# nRF51x22_qfaa_dcdc.net
KiCad netlist of a schematic drawn in EAGLE
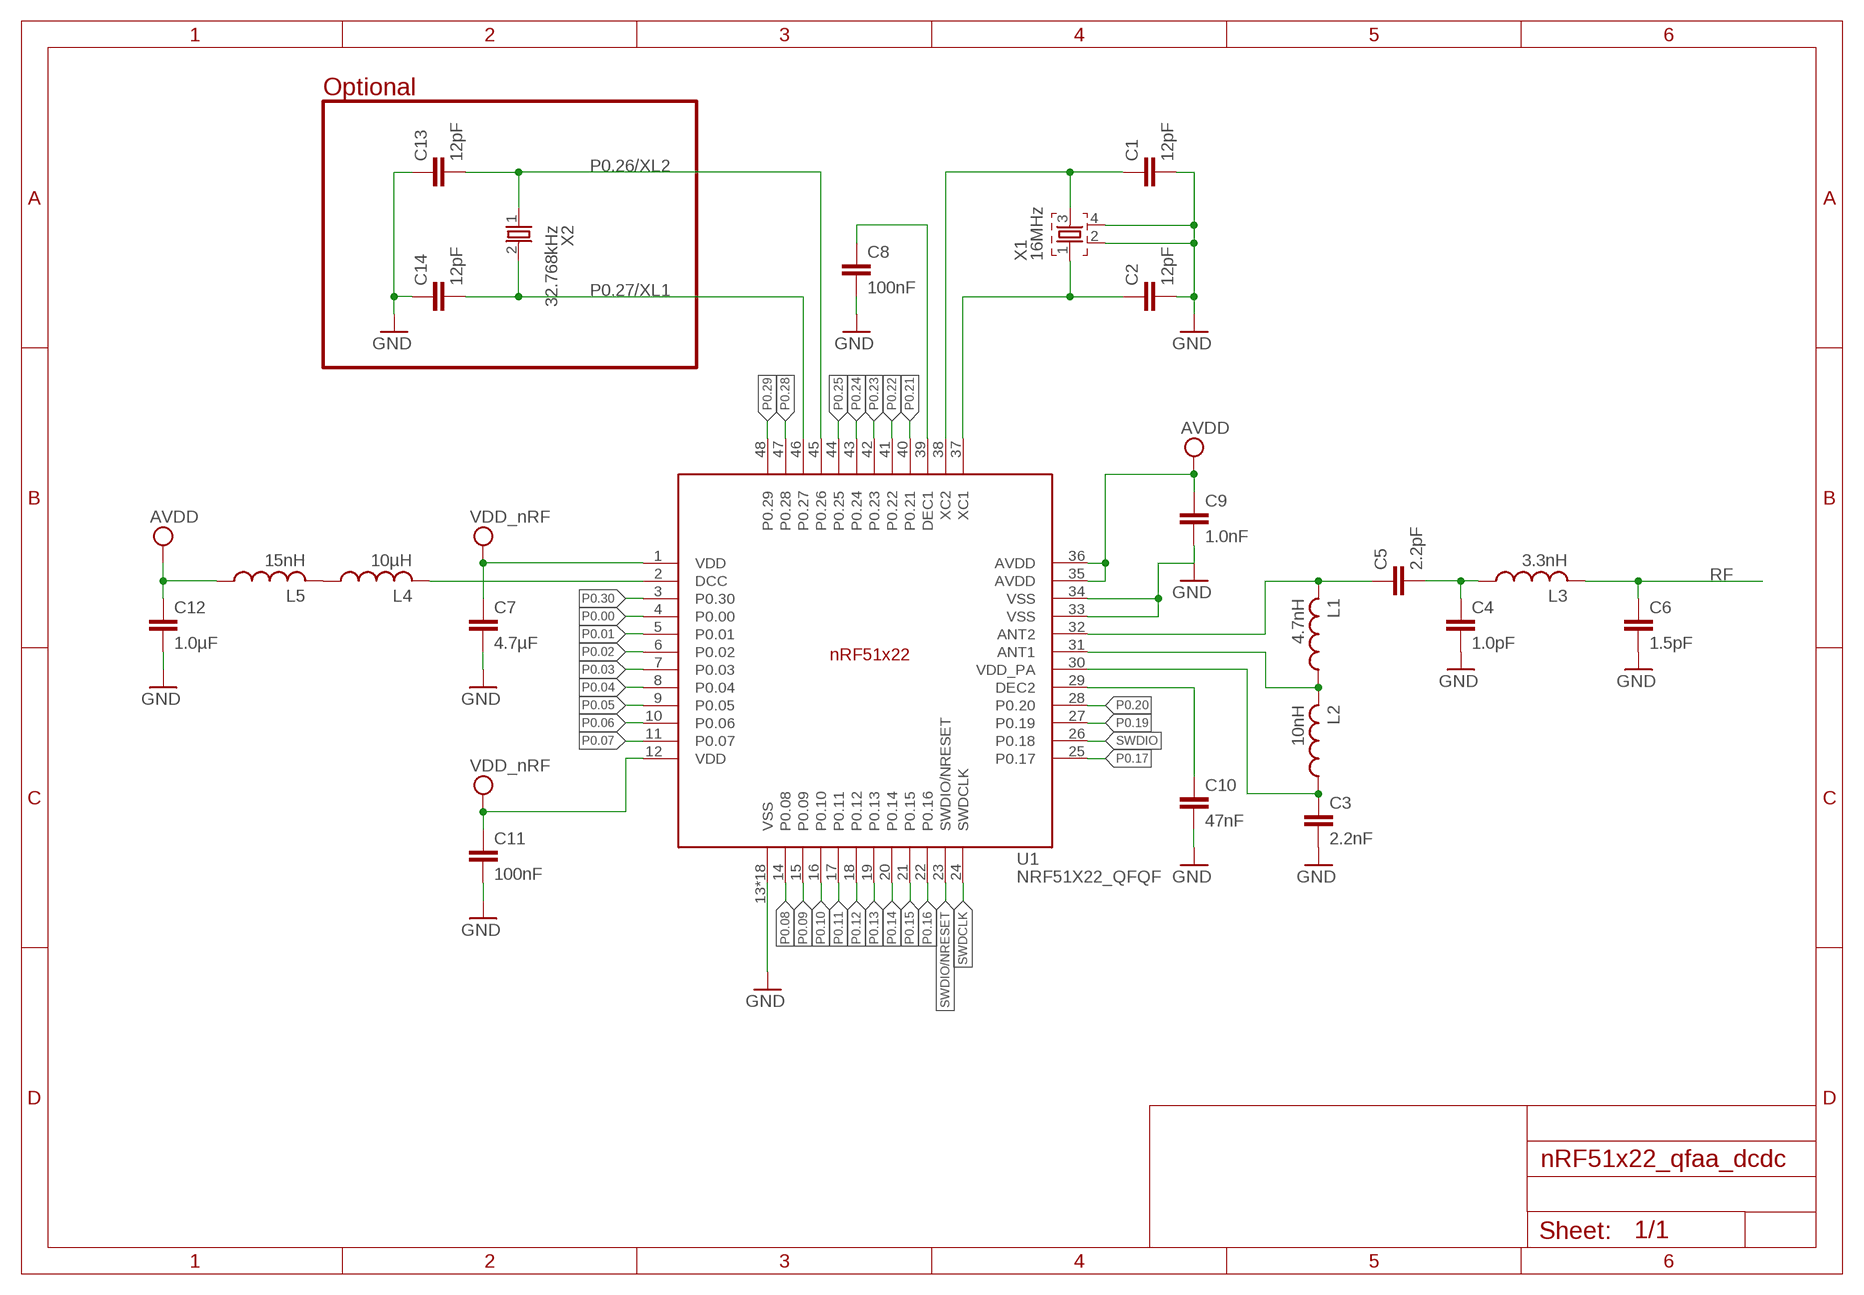
[diagram p0: schematic, sheet 1]

(export (version "E")
  (design (tool "Eeschema 10.0.6"))
  (components
    (comp (ref "C1")
      (value "12pF")
      (footprint "eagle-import:RESC0402_N")
      (libsource (lib "eagle-import") (part "CAPACITOR_0402_N"))
    )
    (comp (ref "C2")
      (value "12pF")
      (footprint "eagle-import:RESC0402_N")
      (libsource (lib "eagle-import") (part "CAPACITOR_0402_N"))
    )
    (comp (ref "C3")
      (value "2.2nF")
      (footprint "eagle-import:RESC0402_N")
      (libsource (lib "eagle-import") (part "CAPACITOR_0402_N"))
    )
    (comp (ref "C4")
      (value "1.0pF")
      (footprint "eagle-import:RESC0402_N")
      (libsource (lib "eagle-import") (part "CAPACITOR_0402_N"))
    )
    (comp (ref "C5")
      (value "2.2pF")
      (footprint "eagle-import:RESC0402_N")
      (libsource (lib "eagle-import") (part "CAPACITOR_0402_N"))
    )
    (comp (ref "C6")
      (value "1.5pF")
      (footprint "eagle-import:RESC0402_N")
      (libsource (lib "eagle-import") (part "CAPACITOR_0402_N"))
    )
    (comp (ref "C7")
      (value "4.7µF")
      (footprint "eagle-import:RESC0603_N")
      (libsource (lib "eagle-import") (part "CAPACITOR_0603_N"))
    )
    (comp (ref "C8")
      (value "100nF")
      (footprint "eagle-import:RESC0402_N")
      (libsource (lib "eagle-import") (part "CAPACITOR_0402_N"))
    )
    (comp (ref "C9")
      (value "1.0nF")
      (footprint "eagle-import:RESC0402_N")
      (libsource (lib "eagle-import") (part "CAPACITOR_0402_N"))
    )
    (comp (ref "C10")
      (value "47nF")
      (footprint "eagle-import:RESC0402_N")
      (libsource (lib "eagle-import") (part "CAPACITOR_0402_N"))
    )
    (comp (ref "C11")
      (value "100nF")
      (footprint "eagle-import:RESC0402_N")
      (libsource (lib "eagle-import") (part "CAPACITOR_0402_N"))
    )
    (comp (ref "C12")
      (value "1.0µF")
      (footprint "eagle-import:RESC0603_N")
      (libsource (lib "eagle-import") (part "CAPACITOR_0603_N"))
    )
    (comp (ref "C13")
      (value "12pF")
      (footprint "eagle-import:RESC0402_N")
      (libsource (lib "eagle-import") (part "CAPACITOR_0402_N"))
    )
    (comp (ref "C14")
      (value "12pF")
      (footprint "eagle-import:RESC0402_N")
      (libsource (lib "eagle-import") (part "CAPACITOR_0402_N"))
    )
    (comp (ref "L1")
      (value "4.7nH")
      (footprint "eagle-import:RESC0402_N")
      (libsource (lib "eagle-import") (part "INDUCTOR_0402_N"))
    )
    (comp (ref "L2")
      (value "10nH")
      (footprint "eagle-import:RESC0402_N")
      (libsource (lib "eagle-import") (part "INDUCTOR_0402_N"))
    )
    (comp (ref "L3")
      (value "3.3nH")
      (footprint "eagle-import:RESC0402_N")
      (libsource (lib "eagle-import") (part "INDUCTOR_0402_N"))
    )
    (comp (ref "L4")
      (value "10µH")
      (footprint "eagle-import:RESC0603_N")
      (libsource (lib "eagle-import") (part "INDUCTOR_0603_N"))
    )
    (comp (ref "L5")
      (value "15nH")
      (footprint "eagle-import:RESC0402_N")
      (libsource (lib "eagle-import") (part "INDUCTOR_0402_N"))
    )
    (comp (ref "U1")
      (value "NRF51X22_QFQF")
      (footprint "eagle-import:QFN40P600X600X90-48_N")
      (libsource (lib "eagle-import") (part "NRF51X22_QFQF"))
    )
    (comp (ref "X1")
      (value "16MHz")
      (footprint "eagle-import:BT-XTAL_2016_N")
      (libsource (lib "eagle-import") (part "XTAL_32MHZ"))
    )
    (comp (ref "X2")
      (value "32.768kHz")
      (footprint "eagle-import:XTAL_3215_N")
      (libsource (lib "eagle-import") (part "XTAL_32KHZ"))
    )
  )
  (nets
    (net (code "1") (name "/P0.26{slash}XL2") (class "Default")
      (node (ref "C13") (pin "2") (pinfunction "2_2") (pintype "passive"))
      (node (ref "U1") (pin "45") (pinfunction "P0.26_45") (pintype "bidirectional"))
      (node (ref "X2") (pin "1") (pinfunction "1_1") (pintype "passive"))
    )
    (net (code "2") (name "/P0.27{slash}XL1") (class "Default")
      (node (ref "C14") (pin "2") (pinfunction "2_2") (pintype "passive"))
      (node (ref "U1") (pin "46") (pinfunction "P0.27_46") (pintype "bidirectional"))
      (node (ref "X2") (pin "2") (pinfunction "2_2") (pintype "passive"))
    )
    (net (code "3") (name "/RF") (class "Default")
      (node (ref "C6") (pin "1") (pinfunction "1_1") (pintype "passive"))
      (node (ref "L3") (pin "2") (pinfunction "2_2") (pintype "passive"))
    )
    (net (code "4") (name "AVDD") (class "Default")
      (node (ref "C12") (pin "1") (pinfunction "1_1") (pintype "passive"))
      (node (ref "C9") (pin "1") (pinfunction "1_1") (pintype "passive"))
      (node (ref "L5") (pin "1") (pinfunction "1_1") (pintype "passive"))
      (node (ref "U1") (pin "35") (pinfunction "AVDD_35") (pintype "power_in"))
      (node (ref "U1") (pin "36") (pinfunction "AVDD_36") (pintype "power_in"))
    )
    (net (code "5") (name "GND") (class "Default")
      (node (ref "C1") (pin "2") (pinfunction "2_2") (pintype "passive"))
      (node (ref "C10") (pin "2") (pinfunction "2_2") (pintype "passive"))
      (node (ref "C11") (pin "2") (pinfunction "2_2") (pintype "passive"))
      (node (ref "C12") (pin "2") (pinfunction "2_2") (pintype "passive"))
      (node (ref "C13") (pin "1") (pinfunction "1_1") (pintype "passive"))
      (node (ref "C14") (pin "1") (pinfunction "1_1") (pintype "passive"))
      (node (ref "C2") (pin "2") (pinfunction "2_2") (pintype "passive"))
      (node (ref "C3") (pin "2") (pinfunction "2_2") (pintype "passive"))
      (node (ref "C4") (pin "2") (pinfunction "2_2") (pintype "passive"))
      (node (ref "C6") (pin "2") (pinfunction "2_2") (pintype "passive"))
      (node (ref "C7") (pin "2") (pinfunction "2_2") (pintype "passive"))
      (node (ref "C8") (pin "2") (pinfunction "2_2") (pintype "passive"))
      (node (ref "C9") (pin "2") (pinfunction "2_2") (pintype "passive"))
      (node (ref "U1") (pin "13") (pinfunction "VSS_13") (pintype "power_in"))
      (node (ref "U1") (pin "33") (pinfunction "VSS_33") (pintype "power_in"))
      (node (ref "U1") (pin "34") (pinfunction "VSS_34") (pintype "power_in"))
      (node (ref "U1") (pin "PAD") (pinfunction "VSS_PAD") (pintype "power_in"))
      (node (ref "U1") (pin "PAD@VIA01") (pinfunction "VSS_PAD@VIA01") (pintype "power_in"))
      (node (ref "U1") (pin "PAD@VIA02") (pinfunction "VSS_PAD@VIA02") (pintype "power_in"))
      (node (ref "U1") (pin "PAD@VIA03") (pinfunction "VSS_PAD@VIA03") (pintype "power_in"))
      (node (ref "U1") (pin "PAD@VIA04") (pinfunction "VSS_PAD@VIA04") (pintype "power_in"))
      (node (ref "U1") (pin "PAD@VIA05") (pinfunction "VSS_PAD@VIA05") (pintype "power_in"))
      (node (ref "U1") (pin "PAD@VIA06") (pinfunction "VSS_PAD@VIA06") (pintype "power_in"))
      (node (ref "U1") (pin "PAD@VIA07") (pinfunction "VSS_PAD@VIA07") (pintype "power_in"))
      (node (ref "U1") (pin "PAD@VIA08") (pinfunction "VSS_PAD@VIA08") (pintype "power_in"))
      (node (ref "U1") (pin "PAD@VIA09") (pinfunction "VSS_PAD@VIA09") (pintype "power_in"))
      (node (ref "U1") (pin "PAD@VIA10") (pinfunction "VSS_PAD@VIA10") (pintype "power_in"))
      (node (ref "U1") (pin "PAD@VIA11") (pinfunction "VSS_PAD@VIA11") (pintype "power_in"))
      (node (ref "U1") (pin "PAD@VIA12") (pinfunction "VSS_PAD@VIA12") (pintype "power_in"))
      (node (ref "U1") (pin "PAD@VIA13") (pinfunction "VSS_PAD@VIA13") (pintype "power_in"))
      (node (ref "U1") (pin "PAD@VIA14") (pinfunction "VSS_PAD@VIA14") (pintype "power_in"))
      (node (ref "U1") (pin "PAD@VIA15") (pinfunction "VSS_PAD@VIA15") (pintype "power_in"))
      (node (ref "U1") (pin "PAD@VIA16") (pinfunction "VSS_PAD@VIA16") (pintype "power_in"))
      (node (ref "X1") (pin "2") (pinfunction "2_2") (pintype "passive"))
      (node (ref "X1") (pin "4") (pinfunction "4_4") (pintype "passive"))
    )
    (net (code "6") (name "Net-(C4-Pad1)") (class "Default")
      (node (ref "C4") (pin "1") (pinfunction "1_1") (pintype "passive"))
      (node (ref "C5") (pin "2") (pinfunction "2_2") (pintype "passive"))
      (node (ref "L3") (pin "1") (pinfunction "1_1") (pintype "passive"))
    )
    (net (code "7") (name "Net-(L4-Pad1)") (class "Default")
      (node (ref "L4") (pin "1") (pinfunction "1_1") (pintype "passive"))
      (node (ref "L5") (pin "2") (pinfunction "2_2") (pintype "passive"))
    )
    (net (code "8") (name "Net-(U1-ANT1)") (class "Default")
      (node (ref "L1") (pin "1") (pinfunction "1_1") (pintype "passive"))
      (node (ref "L2") (pin "2") (pinfunction "2_2") (pintype "passive"))
      (node (ref "U1") (pin "31") (pinfunction "ANT1_31") (pintype "bidirectional"))
    )
    (net (code "9") (name "Net-(U1-ANT2)") (class "Default")
      (node (ref "C5") (pin "1") (pinfunction "1_1") (pintype "passive"))
      (node (ref "L1") (pin "2") (pinfunction "2_2") (pintype "passive"))
      (node (ref "U1") (pin "32") (pinfunction "ANT2_32") (pintype "bidirectional"))
    )
    (net (code "10") (name "Net-(U1-DCC)") (class "Default")
      (node (ref "L4") (pin "2") (pinfunction "2_2") (pintype "passive"))
      (node (ref "U1") (pin "2") (pinfunction "DCC_2") (pintype "power_in"))
    )
    (net (code "11") (name "Net-(U1-DEC1)") (class "Default")
      (node (ref "C8") (pin "1") (pinfunction "1_1") (pintype "passive"))
      (node (ref "U1") (pin "39") (pinfunction "DEC1_39") (pintype "power_in"))
    )
    (net (code "12") (name "Net-(U1-DEC2)") (class "Default")
      (node (ref "C10") (pin "1") (pinfunction "1_1") (pintype "passive"))
      (node (ref "U1") (pin "29") (pinfunction "DEC2_29") (pintype "power_in"))
    )
    (net (code "13") (name "Net-(U1-VDD_PA)") (class "Default")
      (node (ref "C3") (pin "1") (pinfunction "1_1") (pintype "passive"))
      (node (ref "L2") (pin "1") (pinfunction "1_1") (pintype "passive"))
      (node (ref "U1") (pin "30") (pinfunction "VDD_PA_30") (pintype "power_in"))
    )
    (net (code "14") (name "Net-(U1-XC1)") (class "Default")
      (node (ref "C2") (pin "1") (pinfunction "1_1") (pintype "passive"))
      (node (ref "U1") (pin "37") (pinfunction "XC1_37") (pintype "bidirectional"))
      (node (ref "X1") (pin "1") (pinfunction "1_1") (pintype "passive"))
    )
    (net (code "15") (name "Net-(U1-XC2)") (class "Default")
      (node (ref "C1") (pin "1") (pinfunction "1_1") (pintype "passive"))
      (node (ref "U1") (pin "38") (pinfunction "XC2_38") (pintype "bidirectional"))
      (node (ref "X1") (pin "3") (pinfunction "3_3") (pintype "passive"))
    )
    (net (code "16") (name "P0.00") (class "Default")
      (node (ref "U1") (pin "4") (pinfunction "P0.00_4") (pintype "bidirectional"))
    )
    (net (code "17") (name "P0.01") (class "Default")
      (node (ref "U1") (pin "5") (pinfunction "P0.01_5") (pintype "bidirectional"))
    )
    (net (code "18") (name "P0.02") (class "Default")
      (node (ref "U1") (pin "6") (pinfunction "P0.02_6") (pintype "bidirectional"))
    )
    (net (code "19") (name "P0.03") (class "Default")
      (node (ref "U1") (pin "7") (pinfunction "P0.03_7") (pintype "bidirectional"))
    )
    (net (code "20") (name "P0.04") (class "Default")
      (node (ref "U1") (pin "8") (pinfunction "P0.04_8") (pintype "bidirectional"))
    )
    (net (code "21") (name "P0.05") (class "Default")
      (node (ref "U1") (pin "9") (pinfunction "P0.05_9") (pintype "bidirectional"))
    )
    (net (code "22") (name "P0.06") (class "Default")
      (node (ref "U1") (pin "10") (pinfunction "P0.06_10") (pintype "bidirectional"))
    )
    (net (code "23") (name "P0.07") (class "Default")
      (node (ref "U1") (pin "11") (pinfunction "P0.07_11") (pintype "bidirectional"))
    )
    (net (code "24") (name "P0.08") (class "Default")
      (node (ref "U1") (pin "14") (pinfunction "P0.08_14") (pintype "bidirectional"))
    )
    (net (code "25") (name "P0.09") (class "Default")
      (node (ref "U1") (pin "15") (pinfunction "P0.09_15") (pintype "bidirectional"))
    )
    (net (code "26") (name "P0.10") (class "Default")
      (node (ref "U1") (pin "16") (pinfunction "P0.10_16") (pintype "bidirectional"))
    )
    (net (code "27") (name "P0.11") (class "Default")
      (node (ref "U1") (pin "17") (pinfunction "P0.11_17") (pintype "bidirectional"))
    )
    (net (code "28") (name "P0.12") (class "Default")
      (node (ref "U1") (pin "18") (pinfunction "P0.12_18") (pintype "bidirectional"))
    )
    (net (code "29") (name "P0.13") (class "Default")
      (node (ref "U1") (pin "19") (pinfunction "P0.13_19") (pintype "bidirectional"))
    )
    (net (code "30") (name "P0.14") (class "Default")
      (node (ref "U1") (pin "20") (pinfunction "P0.14_20") (pintype "bidirectional"))
    )
    (net (code "31") (name "P0.15") (class "Default")
      (node (ref "U1") (pin "21") (pinfunction "P0.15_21") (pintype "bidirectional"))
    )
    (net (code "32") (name "P0.16") (class "Default")
      (node (ref "U1") (pin "22") (pinfunction "P0.16_22") (pintype "bidirectional"))
    )
    (net (code "33") (name "P0.17") (class "Default")
      (node (ref "U1") (pin "25") (pinfunction "P0.17_25") (pintype "bidirectional"))
    )
    (net (code "34") (name "P0.19") (class "Default")
      (node (ref "U1") (pin "27") (pinfunction "P0.19_27") (pintype "bidirectional"))
    )
    (net (code "35") (name "P0.20") (class "Default")
      (node (ref "U1") (pin "28") (pinfunction "P0.20_28") (pintype "bidirectional"))
    )
    (net (code "36") (name "P0.21") (class "Default")
      (node (ref "U1") (pin "40") (pinfunction "P0.21_40") (pintype "bidirectional"))
    )
    (net (code "37") (name "P0.22") (class "Default")
      (node (ref "U1") (pin "41") (pinfunction "P0.22_41") (pintype "bidirectional"))
    )
    (net (code "38") (name "P0.23") (class "Default")
      (node (ref "U1") (pin "42") (pinfunction "P0.23_42") (pintype "bidirectional"))
    )
    (net (code "39") (name "P0.24") (class "Default")
      (node (ref "U1") (pin "43") (pinfunction "P0.24_43") (pintype "bidirectional"))
    )
    (net (code "40") (name "P0.25") (class "Default")
      (node (ref "U1") (pin "44") (pinfunction "P0.25_44") (pintype "bidirectional"))
    )
    (net (code "41") (name "P0.28") (class "Default")
      (node (ref "U1") (pin "47") (pinfunction "P0.28_47") (pintype "bidirectional"))
    )
    (net (code "42") (name "P0.29") (class "Default")
      (node (ref "U1") (pin "48") (pinfunction "P0.29_48") (pintype "bidirectional"))
    )
    (net (code "43") (name "P0.30") (class "Default")
      (node (ref "U1") (pin "3") (pinfunction "P0.30_3") (pintype "bidirectional"))
    )
    (net (code "44") (name "SWDCLK") (class "Default")
      (node (ref "U1") (pin "24") (pinfunction "SWDCLK_24") (pintype "input"))
    )
    (net (code "45") (name "SWDIO") (class "Default")
      (node (ref "U1") (pin "26") (pinfunction "P0.18_26") (pintype "bidirectional"))
    )
    (net (code "46") (name "SWDIO{slash}NRESET") (class "Default")
      (node (ref "U1") (pin "23") (pinfunction "SWDIO/NRESET_23") (pintype "bidirectional"))
    )
    (net (code "47") (name "VDD_nRF") (class "Default")
      (node (ref "C11") (pin "1") (pinfunction "1_1") (pintype "passive"))
      (node (ref "C7") (pin "1") (pinfunction "1_1") (pintype "passive"))
      (node (ref "U1") (pin "1") (pinfunction "VDD_1") (pintype "power_in"))
      (node (ref "U1") (pin "12") (pinfunction "VDD_12") (pintype "power_in"))
    )
  )
)
